# SX-150_Mk_II.net
KiCad netlist of a schematic drawn in EAGLE
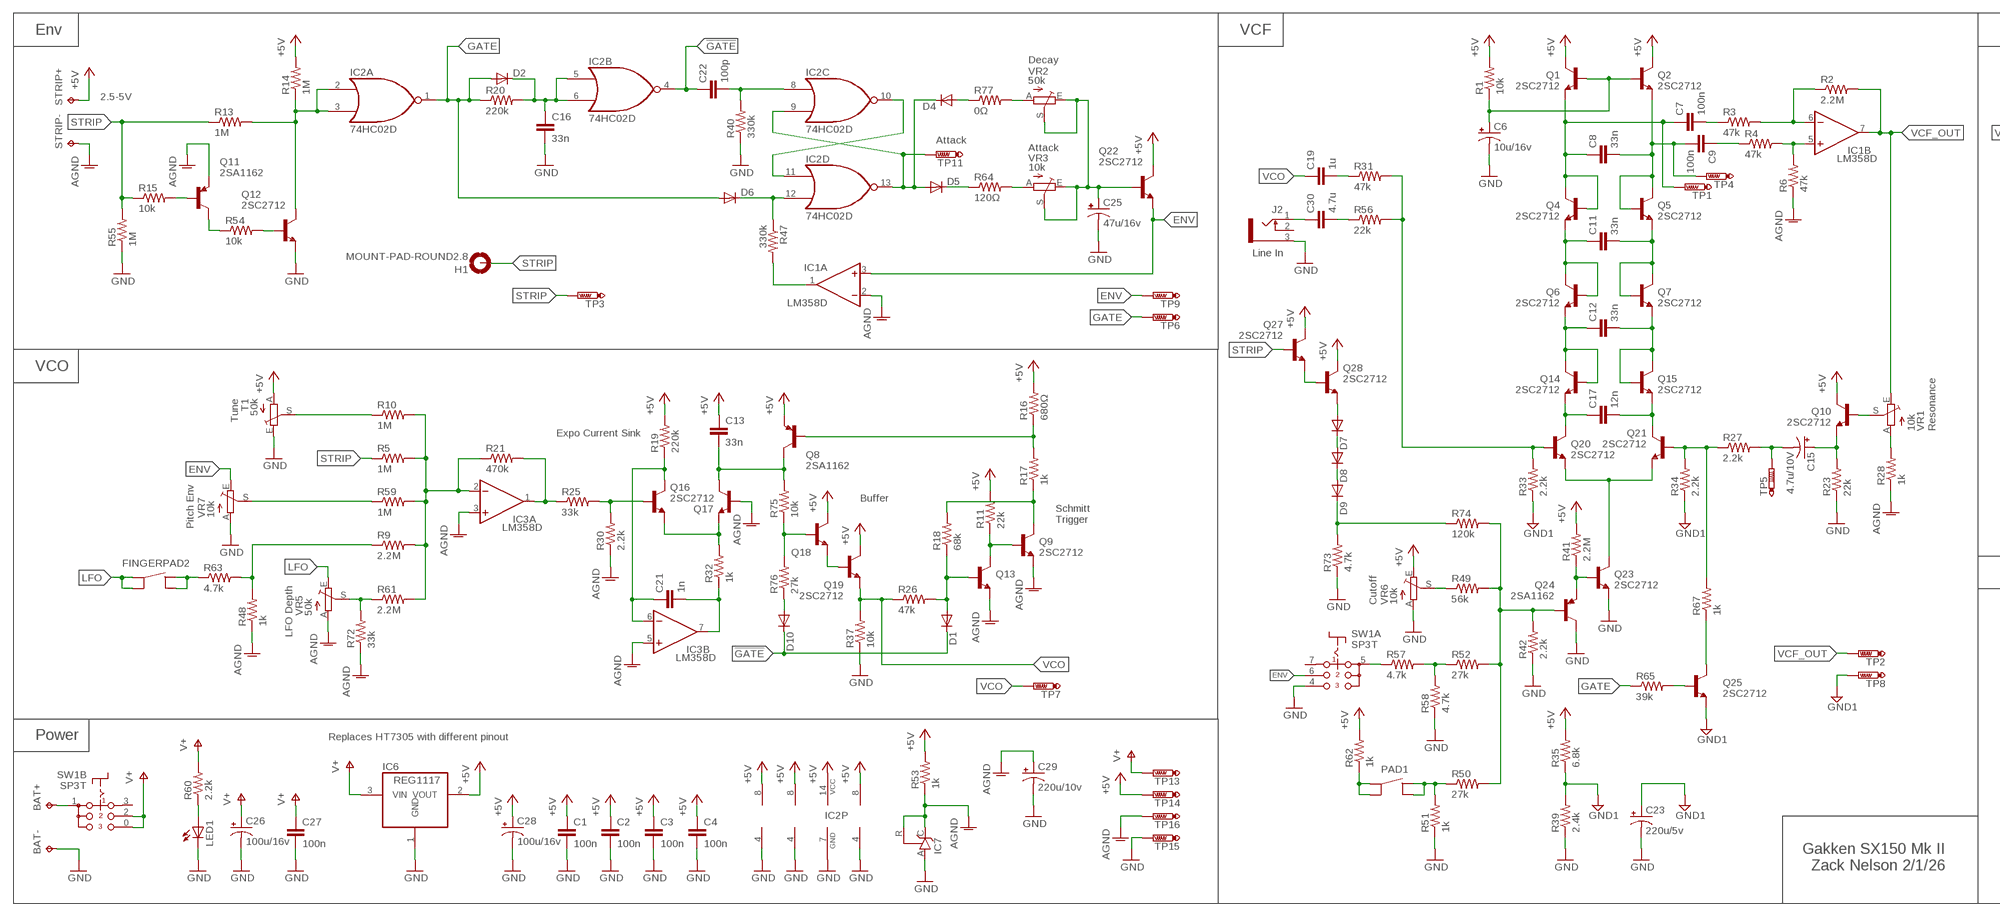
[diagram p0: schematic, sheet 1, part 1 of 2]
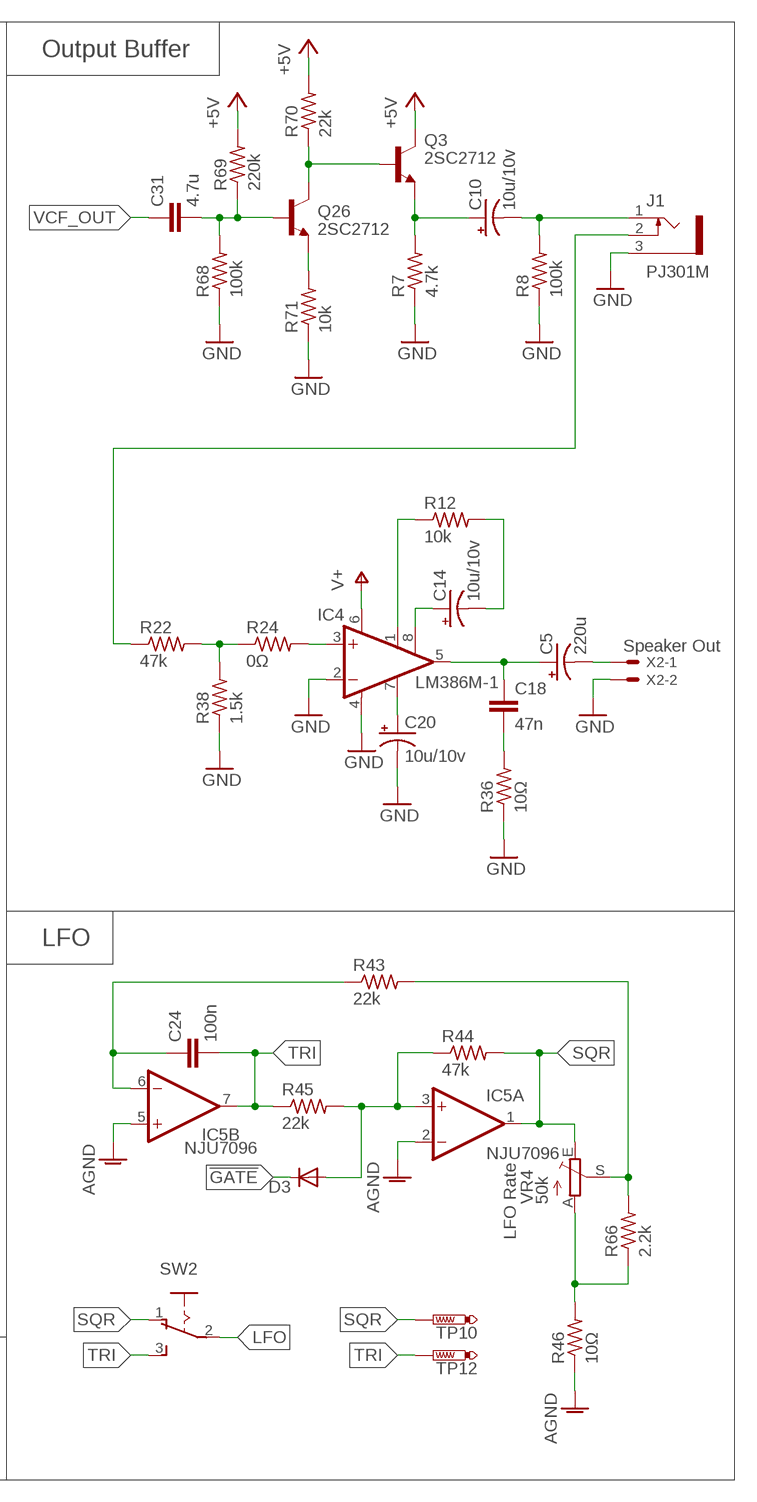
[diagram p1: schematic, sheet 1, part 2 of 2]

(export (version "E")
  (design (tool "Eeschema 10.0.6"))
  (components
    (comp (ref "BAT+")
      (value "TPPAD1-13")
      (footprint "eagle-import:P1-13")
      (libsource (lib "eagle-import") (part "TPPAD1-13"))
    )
    (comp (ref "BAT-")
      (value "TPPAD1-13")
      (footprint "eagle-import:P1-13")
      (libsource (lib "eagle-import") (part "TPPAD1-13"))
    )
    (comp (ref "C1")
      (value "100n")
      (footprint "eagle-import:C0603")
      (libsource (lib "eagle-import") (part "C-EUC0603"))
    )
    (comp (ref "C2")
      (value "100n")
      (footprint "eagle-import:C0603")
      (libsource (lib "eagle-import") (part "C-EUC0603"))
    )
    (comp (ref "C3")
      (value "100n")
      (footprint "eagle-import:C0603")
      (libsource (lib "eagle-import") (part "C-EUC0603"))
    )
    (comp (ref "C4")
      (value "100n")
      (footprint "eagle-import:C0603")
      (libsource (lib "eagle-import") (part "C-EUC0603"))
    )
    (comp (ref "C5")
      (value "220u")
      (footprint "eagle-import:E2,5-6")
      (libsource (lib "eagle-import") (part "CPOL-USE2.5-6"))
    )
    (comp (ref "C6")
      (value "10u/16v")
      (footprint "eagle-import:E2,5-6")
      (libsource (lib "eagle-import") (part "CPOL-USE2.5-6"))
    )
    (comp (ref "C7")
      (value "100n")
      (footprint "eagle-import:C0603")
      (libsource (lib "eagle-import") (part "C-EUC0603"))
    )
    (comp (ref "C8")
      (value "33n")
      (footprint "eagle-import:C0603")
      (libsource (lib "eagle-import") (part "C-EUC0603"))
    )
    (comp (ref "C9")
      (value "100n")
      (footprint "eagle-import:C0603")
      (libsource (lib "eagle-import") (part "C-EUC0603"))
    )
    (comp (ref "C10")
      (value "10u/10v")
      (footprint "eagle-import:E2,5-6")
      (libsource (lib "eagle-import") (part "CPOL-USE2.5-6"))
    )
    (comp (ref "C11")
      (value "33n")
      (footprint "eagle-import:C0603")
      (libsource (lib "eagle-import") (part "C-EUC0603"))
    )
    (comp (ref "C12")
      (value "33n")
      (footprint "eagle-import:C0603")
      (libsource (lib "eagle-import") (part "C-EUC0603"))
    )
    (comp (ref "C13")
      (value "33n")
      (footprint "eagle-import:C0603")
      (libsource (lib "eagle-import") (part "C-EUC0603"))
    )
    (comp (ref "C14")
      (value "10u/10v")
      (footprint "eagle-import:E2,5-6")
      (libsource (lib "eagle-import") (part "CPOL-USE2.5-6"))
    )
    (comp (ref "C15")
      (value "4.7u/10V")
      (footprint "eagle-import:E2,5-6")
      (libsource (lib "eagle-import") (part "CPOL-USE2.5-6"))
    )
    (comp (ref "C16")
      (value "33n")
      (footprint "eagle-import:C0603")
      (libsource (lib "eagle-import") (part "C-EUC0603"))
    )
    (comp (ref "C17")
      (value "12n")
      (footprint "eagle-import:C0603")
      (libsource (lib "eagle-import") (part "C-EUC0603"))
    )
    (comp (ref "C18")
      (value "47n")
      (footprint "eagle-import:C0603")
      (libsource (lib "eagle-import") (part "C-EUC0603"))
    )
    (comp (ref "C19")
      (value "1u")
      (footprint "eagle-import:C0603")
      (libsource (lib "eagle-import") (part "C-EUC0603"))
    )
    (comp (ref "C20")
      (value "10u/10v")
      (footprint "eagle-import:E2,5-6")
      (libsource (lib "eagle-import") (part "CPOL-USE2.5-6"))
    )
    (comp (ref "C21")
      (value "1n")
      (footprint "eagle-import:C0603")
      (libsource (lib "eagle-import") (part "C-EUC0603"))
    )
    (comp (ref "C22")
      (value "100p")
      (footprint "eagle-import:C0603")
      (libsource (lib "eagle-import") (part "C-EUC0603"))
    )
    (comp (ref "C23")
      (value "220u/5v")
      (footprint "eagle-import:E2,5-6")
      (libsource (lib "eagle-import") (part "CPOL-USE2.5-6"))
    )
    (comp (ref "C24")
      (value "100n")
      (footprint "eagle-import:C0603")
      (libsource (lib "eagle-import") (part "C-EUC0603"))
    )
    (comp (ref "C25")
      (value "47u/16v")
      (footprint "eagle-import:E2,5-6")
      (libsource (lib "eagle-import") (part "CPOL-USE2.5-6"))
    )
    (comp (ref "C26")
      (value "100u/16v")
      (footprint "eagle-import:E2,5-6")
      (libsource (lib "eagle-import") (part "CPOL-USE2.5-6"))
    )
    (comp (ref "C27")
      (value "100n")
      (footprint "eagle-import:C0603")
      (libsource (lib "eagle-import") (part "C-EUC0603"))
    )
    (comp (ref "C28")
      (value "100u/16v")
      (footprint "eagle-import:E2,5-6")
      (libsource (lib "eagle-import") (part "CPOL-USE2.5-6"))
    )
    (comp (ref "C29")
      (value "220u/10v")
      (footprint "eagle-import:E2,5-6")
      (libsource (lib "eagle-import") (part "CPOL-USE2.5-6"))
    )
    (comp (ref "C30")
      (value "4.7u")
      (footprint "eagle-import:C0603")
      (libsource (lib "eagle-import") (part "C-EUC0603"))
    )
    (comp (ref "C31")
      (value "4.7u")
      (footprint "eagle-import:C0603")
      (libsource (lib "eagle-import") (part "C-EUC0603"))
    )
    (comp (ref "D1")
      (value "DIODE-DO41-7.6")
      (footprint "eagle-import:DO41-7.6")
      (libsource (lib "eagle-import") (part "DIODE-DO41-7.6"))
    )
    (comp (ref "D2")
      (value "DIODE-MINIMELF")
      (footprint "eagle-import:MINIMELF")
      (libsource (lib "eagle-import") (part "DIODE-MINIMELF"))
    )
    (comp (ref "D3")
      (value "DIODE-MINIMELF")
      (footprint "eagle-import:MINIMELF")
      (libsource (lib "eagle-import") (part "DIODE-MINIMELF"))
    )
    (comp (ref "D4")
      (value "DIODE-MINIMELF")
      (footprint "eagle-import:MINIMELF")
      (libsource (lib "eagle-import") (part "DIODE-MINIMELF"))
    )
    (comp (ref "D5")
      (value "DIODE-MINIMELF")
      (footprint "eagle-import:MINIMELF")
      (libsource (lib "eagle-import") (part "DIODE-MINIMELF"))
    )
    (comp (ref "D6")
      (value "DIODE-MINIMELF")
      (footprint "eagle-import:MINIMELF")
      (libsource (lib "eagle-import") (part "DIODE-MINIMELF"))
    )
    (comp (ref "D7")
      (value "DIODE-MINIMELF")
      (footprint "eagle-import:MINIMELF")
      (libsource (lib "eagle-import") (part "DIODE-MINIMELF"))
    )
    (comp (ref "D8")
      (value "DIODE-MINIMELF")
      (footprint "eagle-import:MINIMELF")
      (libsource (lib "eagle-import") (part "DIODE-MINIMELF"))
    )
    (comp (ref "D9")
      (value "DIODE-MINIMELF")
      (footprint "eagle-import:MINIMELF")
      (libsource (lib "eagle-import") (part "DIODE-MINIMELF"))
    )
    (comp (ref "D10")
      (value "DIODE-DO41-7.6")
      (footprint "eagle-import:DO41-7.6")
      (libsource (lib "eagle-import") (part "DIODE-DO41-7.6"))
    )
    (comp (ref "FINGERPAD2")
      (value "GAKKEN-PAD")
      (footprint "eagle-import:GAKKEN-PAD")
      (libsource (lib "eagle-import") (part "GAKKEN-PAD"))
    )
    (comp (ref "H1")
      (value "MOUNT-PAD-ROUND2.8")
      (footprint "eagle-import:2,8-PAD")
      (libsource (lib "eagle-import") (part "MOUNT-PAD-ROUND2.8"))
    )
    (comp (ref "IC1")
      (value "LM358D")
      (footprint "eagle-import:SO08")
      (libsource (lib "eagle-import") (part "LM358D"))
    )
    (comp (ref "IC2")
      (value "74HC02D")
      (footprint "eagle-import:SO14")
      (libsource (lib "eagle-import") (part "7402D"))
    )
    (comp (ref "IC3")
      (value "LM358D")
      (footprint "eagle-import:SO08")
      (libsource (lib "eagle-import") (part "LM358D"))
    )
    (comp (ref "IC4")
      (value "LM386M-1")
      (footprint "eagle-import:SO08")
      (libsource (lib "eagle-import") (part "LM386?-M1"))
    )
    (comp (ref "IC5")
      (value "NJU7096")
      (footprint "eagle-import:SO08")
      (libsource (lib "eagle-import") (part "LM358D"))
    )
    (comp (ref "IC6")
      (value "REG1117")
      (footprint "eagle-import:SOT223")
      (libsource (lib "eagle-import") (part "REG1117"))
    )
    (comp (ref "IC7")
      (value "TL431CLP")
      (footprint "eagle-import:TO92-CLP")
      (libsource (lib "eagle-import") (part "TL431CLP"))
    )
    (comp (ref "J1")
      (value "PJ301M")
      (footprint "eagle-import:JACK-3.5-NOHOLE")
      (libsource (lib "eagle-import") (part "WQP_PJ301M-12_JACK"))
    )
    (comp (ref "J2")
      (value "Line In")
      (footprint "eagle-import:JACK-3.5-NOHOLE")
      (libsource (lib "eagle-import") (part "WQP_PJ301M-12_JACK"))
    )
    (comp (ref "LED1")
      (value "LED3MM")
      (footprint "eagle-import:LED3MM")
      (libsource (lib "eagle-import") (part "LED3MM"))
    )
    (comp (ref "PAD1")
      (value "GAKKEN-PAD")
      (footprint "eagle-import:GAKKEN-PAD")
      (libsource (lib "eagle-import") (part "GAKKEN-PAD"))
    )
    (comp (ref "Q1")
      (value "2SC2712")
      (footprint "eagle-import:SOT23-BEC")
      (libsource (lib "eagle-import") (part "-NPN-SOT23-BECBC808"))
    )
    (comp (ref "Q2")
      (value "2SC2712")
      (footprint "eagle-import:SOT23-BEC")
      (libsource (lib "eagle-import") (part "-NPN-SOT23-BECBC808"))
    )
    (comp (ref "Q3")
      (value "2SC2712")
      (footprint "eagle-import:SOT23-BEC")
      (libsource (lib "eagle-import") (part "-NPN-SOT23-BECBC808"))
    )
    (comp (ref "Q4")
      (value "2SC2712")
      (footprint "eagle-import:SOT23-BEC")
      (libsource (lib "eagle-import") (part "-NPN-SOT23-BECBC808"))
    )
    (comp (ref "Q5")
      (value "2SC2712")
      (footprint "eagle-import:SOT23-BEC")
      (libsource (lib "eagle-import") (part "-NPN-SOT23-BECBC808"))
    )
    (comp (ref "Q6")
      (value "2SC2712")
      (footprint "eagle-import:SOT23-BEC")
      (libsource (lib "eagle-import") (part "-NPN-SOT23-BECBC808"))
    )
    (comp (ref "Q7")
      (value "2SC2712")
      (footprint "eagle-import:SOT23-BEC")
      (libsource (lib "eagle-import") (part "-NPN-SOT23-BECBC808"))
    )
    (comp (ref "Q8")
      (value "2SA1162")
      (footprint "eagle-import:SOT23-BEC")
      (libsource (lib "eagle-import") (part "-PNP-SOT23-BECBC807-16"))
    )
    (comp (ref "Q9")
      (value "2SC2712")
      (footprint "eagle-import:SOT23-BEC")
      (libsource (lib "eagle-import") (part "-NPN-SOT23-BECBC808"))
    )
    (comp (ref "Q10")
      (value "2SC2712")
      (footprint "eagle-import:SOT23-BEC")
      (libsource (lib "eagle-import") (part "-NPN-SOT23-BECBC808"))
    )
    (comp (ref "Q11")
      (value "2SA1162")
      (footprint "eagle-import:SOT23-BEC")
      (libsource (lib "eagle-import") (part "-PNP-SOT23-BECBC807-16"))
    )
    (comp (ref "Q12")
      (value "2SC2712")
      (footprint "eagle-import:SOT23-BEC")
      (libsource (lib "eagle-import") (part "-NPN-SOT23-BECBC808"))
    )
    (comp (ref "Q13")
      (value "2SC2712")
      (footprint "eagle-import:SOT23-BEC")
      (libsource (lib "eagle-import") (part "-NPN-SOT23-BECBC808"))
    )
    (comp (ref "Q14")
      (value "2SC2712")
      (footprint "eagle-import:SOT23-BEC")
      (libsource (lib "eagle-import") (part "-NPN-SOT23-BECBC808"))
    )
    (comp (ref "Q15")
      (value "2SC2712")
      (footprint "eagle-import:SOT23-BEC")
      (libsource (lib "eagle-import") (part "-NPN-SOT23-BECBC808"))
    )
    (comp (ref "Q16")
      (value "2SC2712")
      (footprint "eagle-import:SOT23-BEC")
      (libsource (lib "eagle-import") (part "-NPN-SOT23-BECBC808"))
    )
    (comp (ref "Q17")
      (value "2SC2712")
      (footprint "eagle-import:SOT23-BEC")
      (libsource (lib "eagle-import") (part "-NPN-SOT23-BECBC808"))
    )
    (comp (ref "Q18")
      (value "2SC2712")
      (footprint "eagle-import:SOT23-BEC")
      (libsource (lib "eagle-import") (part "-NPN-SOT23-BECBC808"))
    )
    (comp (ref "Q19")
      (value "2SC2712")
      (footprint "eagle-import:SOT23-BEC")
      (libsource (lib "eagle-import") (part "-NPN-SOT23-BECBC808"))
    )
    (comp (ref "Q20")
      (value "2SC2712")
      (footprint "eagle-import:SOT23-BEC")
      (libsource (lib "eagle-import") (part "-NPN-SOT23-BECBC808"))
    )
    (comp (ref "Q21")
      (value "2SC2712")
      (footprint "eagle-import:SOT23-BEC")
      (libsource (lib "eagle-import") (part "-NPN-SOT23-BECBC808"))
    )
    (comp (ref "Q22")
      (value "2SC2712")
      (footprint "eagle-import:SOT23-BEC")
      (libsource (lib "eagle-import") (part "-NPN-SOT23-BECBC808"))
    )
    (comp (ref "Q23")
      (value "2SC2712")
      (footprint "eagle-import:SOT23-BEC")
      (libsource (lib "eagle-import") (part "-NPN-SOT23-BECBC808"))
    )
    (comp (ref "Q24")
      (value "2SA1162")
      (footprint "eagle-import:SOT23-BEC")
      (libsource (lib "eagle-import") (part "-PNP-SOT23-BECBC807-16"))
    )
    (comp (ref "Q25")
      (value "2SC2712")
      (footprint "eagle-import:SOT23-BEC")
      (libsource (lib "eagle-import") (part "-NPN-SOT23-BECBC808"))
    )
    (comp (ref "Q26")
      (value "2SC2712")
      (footprint "eagle-import:SOT23-BEC")
      (libsource (lib "eagle-import") (part "-NPN-SOT23-BECBC808"))
    )
    (comp (ref "Q27")
      (value "2SC2712")
      (footprint "eagle-import:SOT23-BEC")
      (libsource (lib "eagle-import") (part "-NPN-SOT23-BECBC808"))
    )
    (comp (ref "Q28")
      (value "2SC2712")
      (footprint "eagle-import:SOT23-BEC")
      (libsource (lib "eagle-import") (part "-NPN-SOT23-BECBC808"))
    )
    (comp (ref "R1")
      (value "10k")
      (footprint "eagle-import:R0603")
      (libsource (lib "eagle-import") (part "R-US_R0603"))
    )
    (comp (ref "R2")
      (value "2.2M")
      (footprint "eagle-import:R0603")
      (libsource (lib "eagle-import") (part "R-US_R0603"))
    )
    (comp (ref "R3")
      (value "47k")
      (footprint "eagle-import:R0603")
      (libsource (lib "eagle-import") (part "R-US_R0603"))
    )
    (comp (ref "R4")
      (value "47k")
      (footprint "eagle-import:R0603")
      (libsource (lib "eagle-import") (part "R-US_R0603"))
    )
    (comp (ref "R5")
      (value "1M")
      (footprint "eagle-import:R0603")
      (libsource (lib "eagle-import") (part "R-US_R0603"))
    )
    (comp (ref "R6")
      (value "47k")
      (footprint "eagle-import:R0603")
      (libsource (lib "eagle-import") (part "R-US_R0603"))
    )
    (comp (ref "R7")
      (value "4.7k")
      (footprint "eagle-import:R0603")
      (libsource (lib "eagle-import") (part "R-US_R0603"))
    )
    (comp (ref "R8")
      (value "100k")
      (footprint "eagle-import:R0603")
      (libsource (lib "eagle-import") (part "R-US_R0603"))
    )
    (comp (ref "R9")
      (value "2.2M")
      (footprint "eagle-import:R0603")
      (libsource (lib "eagle-import") (part "R-US_R0603"))
    )
    (comp (ref "R10")
      (value "1M")
      (footprint "eagle-import:R0603")
      (libsource (lib "eagle-import") (part "R-US_R0603"))
    )
    (comp (ref "R11")
      (value "22k")
      (footprint "eagle-import:R0603")
      (libsource (lib "eagle-import") (part "R-US_R0603"))
    )
    (comp (ref "R12")
      (value "10k")
      (footprint "eagle-import:R0603")
      (libsource (lib "eagle-import") (part "R-US_R0603"))
    )
    (comp (ref "R13")
      (value "1M")
      (footprint "eagle-import:R0603")
      (libsource (lib "eagle-import") (part "R-US_R0603"))
    )
    (comp (ref "R14")
      (value "1M")
      (footprint "eagle-import:R0603")
      (libsource (lib "eagle-import") (part "R-US_R0603"))
    )
    (comp (ref "R15")
      (value "10k")
      (footprint "eagle-import:R0603")
      (libsource (lib "eagle-import") (part "R-US_R0603"))
    )
    (comp (ref "R16")
      (value "680Ω")
      (footprint "eagle-import:R0603")
      (libsource (lib "eagle-import") (part "R-US_R0603"))
    )
    (comp (ref "R17")
      (value "1k")
      (footprint "eagle-import:R0603")
      (libsource (lib "eagle-import") (part "R-US_R0603"))
    )
    (comp (ref "R18")
      (value "68k")
      (footprint "eagle-import:R0603")
      (libsource (lib "eagle-import") (part "R-US_R0603"))
    )
    (comp (ref "R19")
      (value "220k")
      (footprint "eagle-import:R0603")
      (libsource (lib "eagle-import") (part "R-US_R0603"))
    )
    (comp (ref "R20")
      (value "220k")
      (footprint "eagle-import:R0603")
      (libsource (lib "eagle-import") (part "R-US_R0603"))
    )
    (comp (ref "R21")
      (value "470k")
      (footprint "eagle-import:R0603")
      (libsource (lib "eagle-import") (part "R-US_R0603"))
    )
    (comp (ref "R22")
      (value "47k")
      (footprint "eagle-import:R0603")
      (libsource (lib "eagle-import") (part "R-US_R0603"))
    )
    (comp (ref "R23")
      (value "22k")
      (footprint "eagle-import:R0603")
      (libsource (lib "eagle-import") (part "R-US_R0603"))
    )
    (comp (ref "R24")
      (value "0Ω")
      (footprint "eagle-import:R0603")
      (libsource (lib "eagle-import") (part "R-US_R0603"))
    )
    (comp (ref "R25")
      (value "33k")
      (footprint "eagle-import:R0603")
      (libsource (lib "eagle-import") (part "R-US_R0603"))
    )
    (comp (ref "R26")
      (value "47k")
      (footprint "eagle-import:R0603")
      (libsource (lib "eagle-import") (part "R-US_R0603"))
    )
    (comp (ref "R27")
      (value "2.2k")
      (footprint "eagle-import:R0603")
      (libsource (lib "eagle-import") (part "R-US_R0603"))
    )
    (comp (ref "R28")
      (value "1k")
      (footprint "eagle-import:R0603")
      (libsource (lib "eagle-import") (part "R-US_R0603"))
    )
    (comp (ref "R30")
      (value "2.2k")
      (footprint "eagle-import:R0603")
      (libsource (lib "eagle-import") (part "R-US_R0603"))
    )
    (comp (ref "R31")
      (value "47k")
      (footprint "eagle-import:R0603")
      (libsource (lib "eagle-import") (part "R-US_R0603"))
    )
    (comp (ref "R32")
      (value "1k")
      (footprint "eagle-import:R0603")
      (libsource (lib "eagle-import") (part "R-US_R0603"))
    )
    (comp (ref "R33")
      (value "2.2k")
      (footprint "eagle-import:R0603")
      (libsource (lib "eagle-import") (part "R-US_R0603"))
    )
    (comp (ref "R34")
      (value "2.2k")
      (footprint "eagle-import:R0603")
      (libsource (lib "eagle-import") (part "R-US_R0603"))
    )
    (comp (ref "R35")
      (value "6.8k")
      (footprint "eagle-import:R0603")
      (libsource (lib "eagle-import") (part "R-US_R0603"))
    )
    (comp (ref "R36")
      (value "10Ω")
      (footprint "eagle-import:R0603")
      (libsource (lib "eagle-import") (part "R-US_R0603"))
    )
    (comp (ref "R37")
      (value "10k")
      (footprint "eagle-import:R0603")
      (libsource (lib "eagle-import") (part "R-US_R0603"))
    )
    (comp (ref "R38")
      (value "1.5k")
      (footprint "eagle-import:R0603")
      (libsource (lib "eagle-import") (part "R-US_R0603"))
    )
    (comp (ref "R39")
      (value "2.4k")
      (footprint "eagle-import:R0603")
      (libsource (lib "eagle-import") (part "R-US_R0603"))
    )
    (comp (ref "R40")
      (value "330k")
      (footprint "eagle-import:R0603")
      (libsource (lib "eagle-import") (part "R-US_R0603"))
    )
    (comp (ref "R41")
      (value "2.2M")
      (footprint "eagle-import:R0603")
      (libsource (lib "eagle-import") (part "R-US_R0603"))
    )
    (comp (ref "R42")
      (value "2.2k")
      (footprint "eagle-import:R0603")
      (libsource (lib "eagle-import") (part "R-US_R0603"))
    )
    (comp (ref "R43")
      (value "22k")
      (footprint "eagle-import:R0603")
      (libsource (lib "eagle-import") (part "R-US_R0603"))
    )
    (comp (ref "R44")
      (value "47k")
      (footprint "eagle-import:R0603")
      (libsource (lib "eagle-import") (part "R-US_R0603"))
    )
    (comp (ref "R45")
      (value "22k")
      (footprint "eagle-import:R0603")
      (libsource (lib "eagle-import") (part "R-US_R0603"))
    )
    (comp (ref "R46")
      (value "10Ω")
      (footprint "eagle-import:R0603")
      (libsource (lib "eagle-import") (part "R-US_R0603"))
    )
    (comp (ref "R47")
      (value "330k")
      (footprint "eagle-import:R0603")
      (libsource (lib "eagle-import") (part "R-US_R0603"))
    )
    (comp (ref "R48")
      (value "1k")
      (footprint "eagle-import:R0603")
      (libsource (lib "eagle-import") (part "R-US_R0603"))
    )
    (comp (ref "R49")
      (value "56k")
      (footprint "eagle-import:R0603")
      (libsource (lib "eagle-import") (part "R-US_R0603"))
    )
    (comp (ref "R50")
      (value "27k")
      (footprint "eagle-import:R0603")
      (libsource (lib "eagle-import") (part "R-US_R0603"))
    )
    (comp (ref "R51")
      (value "1k")
      (footprint "eagle-import:R0603")
      (libsource (lib "eagle-import") (part "R-US_R0603"))
    )
    (comp (ref "R52")
      (value "27k")
      (footprint "eagle-import:R0603")
      (libsource (lib "eagle-import") (part "R-US_R0603"))
    )
    (comp (ref "R53")
      (value "1k")
      (footprint "eagle-import:R0603")
      (libsource (lib "eagle-import") (part "R-US_R0603"))
    )
    (comp (ref "R54")
      (value "10k")
      (footprint "eagle-import:R0603")
      (libsource (lib "eagle-import") (part "R-US_R0603"))
    )
    (comp (ref "R55")
      (value "1M")
      (footprint "eagle-import:R0603")
      (libsource (lib "eagle-import") (part "R-US_R0603"))
    )
    (comp (ref "R56")
      (value "22k")
      (footprint "eagle-import:R0603")
      (libsource (lib "eagle-import") (part "R-US_R0603"))
    )
    (comp (ref "R57")
      (value "4.7k")
      (footprint "eagle-import:R0603")
      (libsource (lib "eagle-import") (part "R-US_R0603"))
    )
    (comp (ref "R58")
      (value "4.7k")
      (footprint "eagle-import:R0603")
      (libsource (lib "eagle-import") (part "R-US_R0603"))
    )
    (comp (ref "R59")
      (value "1M")
      (footprint "eagle-import:R0603")
      (libsource (lib "eagle-import") (part "R-US_R0603"))
    )
    (comp (ref "R60")
      (value "2.2k")
      (footprint "eagle-import:R0603")
      (libsource (lib "eagle-import") (part "R-US_R0603"))
    )
    (comp (ref "R61")
      (value "2.2M")
      (footprint "eagle-import:R0603")
      (libsource (lib "eagle-import") (part "R-US_R0603"))
    )
    (comp (ref "R62")
      (value "1k")
      (footprint "eagle-import:R0603")
      (libsource (lib "eagle-import") (part "R-US_R0603"))
    )
    (comp (ref "R63")
      (value "4.7k")
      (footprint "eagle-import:R0603")
      (libsource (lib "eagle-import") (part "R-US_R0603"))
    )
    (comp (ref "R64")
      (value "120Ω")
      (footprint "eagle-import:R0603")
      (libsource (lib "eagle-import") (part "R-US_R0603"))
    )
    (comp (ref "R65")
      (value "39k")
      (footprint "eagle-import:R0603")
      (libsource (lib "eagle-import") (part "R-US_R0603"))
    )
    (comp (ref "R66")
      (value "2.2k")
      (footprint "eagle-import:R0603")
      (libsource (lib "eagle-import") (part "R-US_R0603"))
    )
    (comp (ref "R67")
      (value "1k")
      (footprint "eagle-import:R0603")
      (libsource (lib "eagle-import") (part "R-US_R0603"))
    )
    (comp (ref "R68")
      (value "100k")
      (footprint "eagle-import:R0603")
      (libsource (lib "eagle-import") (part "R-US_R0603"))
    )
    (comp (ref "R69")
      (value "220k")
      (footprint "eagle-import:R0603")
      (libsource (lib "eagle-import") (part "R-US_R0603"))
    )
    (comp (ref "R70")
      (value "22k")
      (footprint "eagle-import:R0603")
      (libsource (lib "eagle-import") (part "R-US_R0603"))
    )
    (comp (ref "R71")
      (value "10k")
      (footprint "eagle-import:R0603")
      (libsource (lib "eagle-import") (part "R-US_R0603"))
    )
    (comp (ref "R72")
      (value "33k")
      (footprint "eagle-import:R0603")
      (libsource (lib "eagle-import") (part "R-US_R0603"))
    )
    (comp (ref "R73")
      (value "4.7k")
      (footprint "eagle-import:R0603")
      (libsource (lib "eagle-import") (part "R-US_R0603"))
    )
    (comp (ref "R74")
      (value "120k")
      (footprint "eagle-import:R0603")
      (libsource (lib "eagle-import") (part "R-US_R0603"))
    )
    (comp (ref "R75")
      (value "10k")
      (footprint "eagle-import:R0603")
      (libsource (lib "eagle-import") (part "R-US_R0603"))
    )
    (comp (ref "R76")
      (value "27k")
      (footprint "eagle-import:R0603")
      (libsource (lib "eagle-import") (part "R-US_R0603"))
    )
    (comp (ref "R77")
      (value "0Ω")
      (footprint "eagle-import:R0603")
      (libsource (lib "eagle-import") (part "R-US_R0603"))
    )
    (comp (ref "STRIP+")
      (value "TPB1,27")
      (footprint "eagle-import:B1,27")
      (libsource (lib "eagle-import") (part "TPB1,27"))
    )
    (comp (ref "STRIP-")
      (value "TPB1,27")
      (footprint "eagle-import:B1,27")
      (libsource (lib "eagle-import") (part "TPB1,27"))
    )
    (comp (ref "SW1")
      (value "SP3T")
      (footprint "eagle-import:SP3T")
      (libsource (lib "eagle-import") (part "SP3T"))
    )
    (comp (ref "SW2")
      (value "M251")
      (footprint "eagle-import:M251")
      (libsource (lib "eagle-import") (part "M251"))
    )
    (comp (ref "T1")
      (value "50k")
      (footprint "eagle-import:CA9V")
      (libsource (lib "eagle-import") (part "TRIM_EU-CA9V"))
    )
    (comp (ref "TP1")
      (value "PTR1B1,27")
      (footprint "eagle-import:B1,27")
      (libsource (lib "eagle-import") (part "PTR1B1,27"))
    )
    (comp (ref "TP2")
      (value "PTR1B1,27")
      (footprint "eagle-import:B1,27")
      (libsource (lib "eagle-import") (part "PTR1B1,27"))
    )
    (comp (ref "TP3")
      (value "PTR1B1,27")
      (footprint "eagle-import:B1,27")
      (libsource (lib "eagle-import") (part "PTR1B1,27"))
    )
    (comp (ref "TP4")
      (value "PTR1B1,27")
      (footprint "eagle-import:B1,27")
      (libsource (lib "eagle-import") (part "PTR1B1,27"))
    )
    (comp (ref "TP5")
      (value "PTR1B1,27")
      (footprint "eagle-import:B1,27")
      (libsource (lib "eagle-import") (part "PTR1B1,27"))
    )
    (comp (ref "TP6")
      (value "PTR1B1,27")
      (footprint "eagle-import:B1,27")
      (libsource (lib "eagle-import") (part "PTR1B1,27"))
    )
    (comp (ref "TP7")
      (value "PTR1B1,27")
      (footprint "eagle-import:B1,27")
      (libsource (lib "eagle-import") (part "PTR1B1,27"))
    )
    (comp (ref "TP8")
      (value "PTR1B1,27")
      (footprint "eagle-import:B1,27")
      (libsource (lib "eagle-import") (part "PTR1B1,27"))
    )
    (comp (ref "TP9")
      (value "PTR1B1,27")
      (footprint "eagle-import:B1,27")
      (libsource (lib "eagle-import") (part "PTR1B1,27"))
    )
    (comp (ref "TP10")
      (value "PTR1B1,27")
      (footprint "eagle-import:B1,27")
      (libsource (lib "eagle-import") (part "PTR1B1,27"))
    )
    (comp (ref "TP11")
      (value "PTR1B1,27")
      (footprint "eagle-import:B1,27")
      (libsource (lib "eagle-import") (part "PTR1B1,27"))
    )
    (comp (ref "TP12")
      (value "PTR1B1,27")
      (footprint "eagle-import:B1,27")
      (libsource (lib "eagle-import") (part "PTR1B1,27"))
    )
    (comp (ref "TP13")
      (value "PTR1B1,27")
      (footprint "eagle-import:B1,27")
      (libsource (lib "eagle-import") (part "PTR1B1,27"))
    )
    (comp (ref "TP14")
      (value "PTR1B1,27")
      (footprint "eagle-import:B1,27")
      (libsource (lib "eagle-import") (part "PTR1B1,27"))
    )
    (comp (ref "TP15")
      (value "PTR1B1,27")
      (footprint "eagle-import:B1,27")
      (libsource (lib "eagle-import") (part "PTR1B1,27"))
    )
    (comp (ref "TP16")
      (value "PTR1B1,27")
      (footprint "eagle-import:B1,27")
      (libsource (lib "eagle-import") (part "PTR1B1,27"))
    )
    (comp (ref "VR1")
      (value "10k")
      (footprint "eagle-import:CA9V")
      (libsource (lib "eagle-import") (part "TRIM_EU-CA9V"))
    )
    (comp (ref "VR2")
      (value "50k")
      (footprint "eagle-import:CA9V")
      (libsource (lib "eagle-import") (part "TRIM_EU-CA9V"))
    )
    (comp (ref "VR3")
      (value "10k")
      (footprint "eagle-import:CA9V")
      (libsource (lib "eagle-import") (part "TRIM_EU-CA9V"))
    )
    (comp (ref "VR4")
      (value "50k")
      (footprint "eagle-import:CA9V")
      (libsource (lib "eagle-import") (part "TRIM_EU-CA9V"))
    )
    (comp (ref "VR5")
      (value "50k")
      (footprint "eagle-import:CA9V")
      (libsource (lib "eagle-import") (part "TRIM_EU-CA9V"))
    )
    (comp (ref "VR6")
      (value "10k")
      (footprint "eagle-import:CA9V")
      (libsource (lib "eagle-import") (part "TRIM_EU-CA9V"))
    )
    (comp (ref "VR7")
      (value "10k")
      (footprint "eagle-import:CA9V")
      (libsource (lib "eagle-import") (part "TRIM_EU-CA9V"))
    )
    (comp (ref "X2")
      (value "Speaker Out")
      (footprint "eagle-import:22-23-2021")
      (fields (field (name "MF") "MOLEX") (field (name "MPN") "22-23-2021"))
      (libsource (lib "eagle-import") (part "22-23-2021"))
    )
  )
  (nets
    (net (code "1") (name "+5V") (class "Default")
      (node (ref "C1") (pin "1") (pinfunction "1_1") (pintype "passive"))
      (node (ref "C13") (pin "1") (pinfunction "1_1") (pintype "passive"))
      (node (ref "C2") (pin "1") (pinfunction "1_1") (pintype "passive"))
      (node (ref "C28") (pin "+") (pinfunction "+_+") (pintype "passive"))
      (node (ref "C3") (pin "1") (pinfunction "1_1") (pintype "passive"))
      (node (ref "C4") (pin "1") (pinfunction "1_1") (pintype "passive"))
      (node (ref "IC1") (pin "8") (pinfunction "V+_8") (pintype "power_in"))
      (node (ref "IC2") (pin "14") (pinfunction "VCC_14") (pintype "power_in"))
      (node (ref "IC3") (pin "8") (pinfunction "V+_8") (pintype "power_in"))
      (node (ref "IC5") (pin "8") (pinfunction "V+_8") (pintype "power_in"))
      (node (ref "IC6") (pin "2") (pinfunction "VOUT_2") (pintype "output"))
      (node (ref "Q1") (pin "C") (pinfunction "C_C") (pintype "passive"))
      (node (ref "Q10") (pin "C") (pinfunction "C_C") (pintype "passive"))
      (node (ref "Q18") (pin "C") (pinfunction "C_C") (pintype "passive"))
      (node (ref "Q19") (pin "C") (pinfunction "C_C") (pintype "passive"))
      (node (ref "Q2") (pin "C") (pinfunction "C_C") (pintype "passive"))
      (node (ref "Q22") (pin "C") (pinfunction "C_C") (pintype "passive"))
      (node (ref "Q27") (pin "C") (pinfunction "C_C") (pintype "passive"))
      (node (ref "Q28") (pin "C") (pinfunction "C_C") (pintype "passive"))
      (node (ref "Q3") (pin "C") (pinfunction "C_C") (pintype "passive"))
      (node (ref "Q8") (pin "E") (pinfunction "E_E") (pintype "passive"))
      (node (ref "R1") (pin "2") (pinfunction "2_2") (pintype "passive"))
      (node (ref "R11") (pin "2") (pinfunction "2_2") (pintype "passive"))
      (node (ref "R14") (pin "2") (pinfunction "2_2") (pintype "passive"))
      (node (ref "R16") (pin "2") (pinfunction "2_2") (pintype "passive"))
      (node (ref "R19") (pin "2") (pinfunction "2_2") (pintype "passive"))
      (node (ref "R35") (pin "2") (pinfunction "2_2") (pintype "passive"))
      (node (ref "R41") (pin "2") (pinfunction "2_2") (pintype "passive"))
      (node (ref "R53") (pin "2") (pinfunction "2_2") (pintype "passive"))
      (node (ref "R62") (pin "2") (pinfunction "2_2") (pintype "passive"))
      (node (ref "R69") (pin "2") (pinfunction "2_2") (pintype "passive"))
      (node (ref "R70") (pin "2") (pinfunction "2_2") (pintype "passive"))
      (node (ref "STRIP+") (pin "TP") (pinfunction "TP_TP") (pintype "input"))
      (node (ref "T1") (pin "A") (pinfunction "A_A") (pintype "passive"))
      (node (ref "TP14") (pin "TP") (pinfunction "TP_TP") (pintype "input"))
      (node (ref "VR6") (pin "E") (pinfunction "E_E") (pintype "passive"))
    )
    (net (code "2") (name "/~{GATE}") (class "Default")
      (node (ref "C22") (pin "1") (pinfunction "1_1") (pintype "passive"))
      (node (ref "D1") (pin "C") (pinfunction "C_C") (pintype "passive"))
      (node (ref "D10") (pin "C") (pinfunction "C_C") (pintype "passive"))
      (node (ref "D3") (pin "C") (pinfunction "C_C") (pintype "passive"))
      (node (ref "IC2") (pin "4") (pinfunction "O_4") (pintype "output"))
    )
    (net (code "3") (name "AGND") (class "Default")
      (node (ref "C29") (pin "+") (pinfunction "+_+") (pintype "passive"))
      (node (ref "IC1") (pin "2") (pinfunction "-IN_2") (pintype "input"))
      (node (ref "IC3") (pin "3") (pinfunction "+IN_3") (pintype "input"))
      (node (ref "IC3") (pin "5") (pinfunction "+IN_5") (pintype "input"))
      (node (ref "IC5") (pin "2") (pinfunction "-IN_2") (pintype "input"))
      (node (ref "IC5") (pin "5") (pinfunction "+IN_5") (pintype "input"))
      (node (ref "IC7") (pin "C") (pinfunction "C_C") (pintype "passive"))
      (node (ref "IC7") (pin "R") (pinfunction "R_R") (pintype "passive"))
      (node (ref "Q11") (pin "E") (pinfunction "E_E") (pintype "passive"))
      (node (ref "Q13") (pin "E") (pinfunction "E_E") (pintype "passive"))
      (node (ref "Q17") (pin "B") (pinfunction "B_B") (pintype "passive"))
      (node (ref "Q9") (pin "E") (pinfunction "E_E") (pintype "passive"))
      (node (ref "R28") (pin "1") (pinfunction "1_1") (pintype "passive"))
      (node (ref "R30") (pin "1") (pinfunction "1_1") (pintype "passive"))
      (node (ref "R46") (pin "1") (pinfunction "1_1") (pintype "passive"))
      (node (ref "R48") (pin "1") (pinfunction "1_1") (pintype "passive"))
      (node (ref "R53") (pin "1") (pinfunction "1_1") (pintype "passive"))
      (node (ref "R6") (pin "1") (pinfunction "1_1") (pintype "passive"))
      (node (ref "R72") (pin "1") (pinfunction "1_1") (pintype "passive"))
      (node (ref "STRIP-") (pin "TP") (pinfunction "TP_TP") (pintype "input"))
      (node (ref "TP16") (pin "TP") (pinfunction "TP_TP") (pintype "input"))
      (node (ref "VR5") (pin "A") (pinfunction "A_A") (pintype "passive"))
    )
    (net (code "4") (name "ENV") (class "Default")
      (node (ref "IC1") (pin "3") (pinfunction "+IN_3") (pintype "input"))
      (node (ref "Q22") (pin "E") (pinfunction "E_E") (pintype "passive"))
      (node (ref "SW1") (pin "6") (pinfunction "T2_6") (pintype "passive"))
      (node (ref "TP9") (pin "TP") (pinfunction "TP_TP") (pintype "input"))
      (node (ref "VR7") (pin "E") (pinfunction "E_E") (pintype "passive"))
    )
    (net (code "5") (name "GATE") (class "Default")
      (node (ref "D2") (pin "A") (pinfunction "A_A") (pintype "passive"))
      (node (ref "D6") (pin "A") (pinfunction "A_A") (pintype "passive"))
      (node (ref "IC2") (pin "1") (pinfunction "O_1") (pintype "output"))
      (node (ref "R20") (pin "1") (pinfunction "1_1") (pintype "passive"))
      (node (ref "R65") (pin "1") (pinfunction "1_1") (pintype "passive"))
      (node (ref "TP6") (pin "TP") (pinfunction "TP_TP") (pintype "input"))
    )
    (net (code "6") (name "GND") (class "Default")
      (node (ref "BAT-") (pin "TP") (pinfunction "TP_TP") (pintype "input"))
      (node (ref "C1") (pin "2") (pinfunction "2_2") (pintype "passive"))
      (node (ref "C16") (pin "2") (pinfunction "2_2") (pintype "passive"))
      (node (ref "C2") (pin "2") (pinfunction "2_2") (pintype "passive"))
      (node (ref "C20") (pin "-") (pinfunction "-_-") (pintype "passive"))
      (node (ref "C23") (pin "-") (pinfunction "-_-") (pintype "passive"))
      (node (ref "C25") (pin "-") (pinfunction "-_-") (pintype "passive"))
      (node (ref "C26") (pin "-") (pinfunction "-_-") (pintype "passive"))
      (node (ref "C27") (pin "2") (pinfunction "2_2") (pintype "passive"))
      (node (ref "C28") (pin "-") (pinfunction "-_-") (pintype "passive"))
      (node (ref "C29") (pin "-") (pinfunction "-_-") (pintype "passive"))
      (node (ref "C3") (pin "2") (pinfunction "2_2") (pintype "passive"))
      (node (ref "C4") (pin "2") (pinfunction "2_2") (pintype "passive"))
      (node (ref "C6") (pin "-") (pinfunction "-_-") (pintype "passive"))
      (node (ref "IC1") (pin "4") (pinfunction "V-_4") (pintype "power_in"))
      (node (ref "IC2") (pin "7") (pinfunction "GND_7") (pintype "power_in"))
      (node (ref "IC3") (pin "4") (pinfunction "V-_4") (pintype "power_in"))
      (node (ref "IC4") (pin "2") (pinfunction "-IN_2") (pintype "input"))
      (node (ref "IC4") (pin "4") (pinfunction "GND_4") (pintype "power_in"))
      (node (ref "IC5") (pin "4") (pinfunction "V-_4") (pintype "power_in"))
      (node (ref "IC6") (pin "1") (pinfunction "GND_1") (pintype "power_in"))
      (node (ref "IC7") (pin "A") (pinfunction "A_A") (pintype "passive"))
      (node (ref "J1") (pin "3") (pinfunction "1_3") (pintype "passive"))
      (node (ref "J2") (pin "3") (pinfunction "1_3") (pintype "passive"))
      (node (ref "LED1") (pin "K") (pinfunction "C_K") (pintype "passive"))
      (node (ref "Q12") (pin "E") (pinfunction "E_E") (pintype "passive"))
      (node (ref "Q23") (pin "E") (pinfunction "E_E") (pintype "passive"))
      (node (ref "Q24") (pin "C") (pinfunction "C_C") (pintype "passive"))
      (node (ref "R23") (pin "1") (pinfunction "1_1") (pintype "passive"))
      (node (ref "R36") (pin "1") (pinfunction "1_1") (pintype "passive"))
      (node (ref "R37") (pin "1") (pinfunction "1_1") (pintype "passive"))
      (node (ref "R38") (pin "1") (pinfunction "1_1") (pintype "passive"))
      (node (ref "R39") (pin "1") (pinfunction "1_1") (pintype "passive"))
      (node (ref "R40") (pin "1") (pinfunction "1_1") (pintype "passive"))
      (node (ref "R42") (pin "1") (pinfunction "1_1") (pintype "passive"))
      (node (ref "R51") (pin "1") (pinfunction "1_1") (pintype "passive"))
      (node (ref "R55") (pin "1") (pinfunction "1_1") (pintype "passive"))
      (node (ref "R58") (pin "1") (pinfunction "1_1") (pintype "passive"))
      (node (ref "R68") (pin "1") (pinfunction "1_1") (pintype "passive"))
      (node (ref "R7") (pin "1") (pinfunction "1_1") (pintype "passive"))
      (node (ref "R71") (pin "1") (pinfunction "1_1") (pintype "passive"))
      (node (ref "R73") (pin "1") (pinfunction "1_1") (pintype "passive"))
      (node (ref "R8") (pin "1") (pinfunction "1_1") (pintype "passive"))
      (node (ref "SW1") (pin "4") (pinfunction "T3_4") (pintype "passive"))
      (node (ref "T1") (pin "E") (pinfunction "E_E") (pintype "passive"))
      (node (ref "TP15") (pin "TP") (pinfunction "TP_TP") (pintype "input"))
      (node (ref "VR6") (pin "A") (pinfunction "A_A") (pintype "passive"))
      (node (ref "VR7") (pin "A") (pinfunction "A_A") (pintype "passive"))
      (node (ref "X2") (pin "2") (pinfunction "S_2") (pintype "passive"))
    )
    (net (code "7") (name "GND1") (class "Default")
      (node (ref "C23") (pin "+") (pinfunction "+_+") (pintype "passive"))
      (node (ref "Q25") (pin "E") (pinfunction "E_E") (pintype "passive"))
      (node (ref "R33") (pin "1") (pinfunction "1_1") (pintype "passive"))
      (node (ref "R34") (pin "1") (pinfunction "1_1") (pintype "passive"))
      (node (ref "R35") (pin "1") (pinfunction "1_1") (pintype "passive"))
      (node (ref "R39") (pin "2") (pinfunction "2_2") (pintype "passive"))
      (node (ref "TP8") (pin "TP") (pinfunction "TP_TP") (pintype "input"))
    )
    (net (code "8") (name "LFO") (class "Default")
      (node (ref "FINGERPAD2") (pin "A0") (pinfunction "A0_A0") (pintype "passive"))
      (node (ref "FINGERPAD2") (pin "A1") (pinfunction "A1_A1") (pintype "passive"))
      (node (ref "SW2") (pin "2") (pinfunction "P_2") (pintype "passive"))
      (node (ref "VR5") (pin "E") (pinfunction "E_E") (pintype "passive"))
    )
    (net (code "9") (name "Net-(C6-Pad+)") (class "Default")
      (node (ref "C6") (pin "+") (pinfunction "+_+") (pintype "passive"))
      (node (ref "Q1") (pin "B") (pinfunction "B_B") (pintype "passive"))
      (node (ref "Q2") (pin "B") (pinfunction "B_B") (pintype "passive"))
      (node (ref "R1") (pin "1") (pinfunction "1_1") (pintype "passive"))
    )
    (net (code "10") (name "Net-(C7-Pad1)") (class "Default")
      (node (ref "C7") (pin "1") (pinfunction "1_1") (pintype "passive"))
      (node (ref "C8") (pin "1") (pinfunction "1_1") (pintype "passive"))
      (node (ref "Q1") (pin "E") (pinfunction "E_E") (pintype "passive"))
      (node (ref "Q4") (pin "B") (pinfunction "B_B") (pintype "passive"))
      (node (ref "Q4") (pin "C") (pinfunction "C_C") (pintype "passive"))
      (node (ref "TP1") (pin "TP") (pinfunction "TP_TP") (pintype "input"))
    )
    (net (code "11") (name "Net-(C7-Pad2)") (class "Default")
      (node (ref "C7") (pin "2") (pinfunction "2_2") (pintype "passive"))
      (node (ref "R3") (pin "1") (pinfunction "1_1") (pintype "passive"))
    )
    (net (code "12") (name "Net-(C8-Pad2)") (class "Default")
      (node (ref "C8") (pin "2") (pinfunction "2_2") (pintype "passive"))
      (node (ref "C9") (pin "2") (pinfunction "2_2") (pintype "passive"))
      (node (ref "Q2") (pin "E") (pinfunction "E_E") (pintype "passive"))
      (node (ref "Q5") (pin "B") (pinfunction "B_B") (pintype "passive"))
      (node (ref "Q5") (pin "C") (pinfunction "C_C") (pintype "passive"))
      (node (ref "TP4") (pin "TP") (pinfunction "TP_TP") (pintype "input"))
    )
    (net (code "13") (name "Net-(C9-Pad1)") (class "Default")
      (node (ref "C9") (pin "1") (pinfunction "1_1") (pintype "passive"))
      (node (ref "R4") (pin "1") (pinfunction "1_1") (pintype "passive"))
    )
    (net (code "14") (name "Net-(C10-Pad+)") (class "Default")
      (node (ref "C10") (pin "+") (pinfunction "+_+") (pintype "passive"))
      (node (ref "Q3") (pin "E") (pinfunction "E_E") (pintype "passive"))
      (node (ref "R7") (pin "2") (pinfunction "2_2") (pintype "passive"))
    )
    (net (code "15") (name "Net-(C11-Pad1)") (class "Default")
      (node (ref "C11") (pin "1") (pinfunction "1_1") (pintype "passive"))
      (node (ref "Q4") (pin "E") (pinfunction "E_E") (pintype "passive"))
      (node (ref "Q6") (pin "B") (pinfunction "B_B") (pintype "passive"))
      (node (ref "Q6") (pin "C") (pinfunction "C_C") (pintype "passive"))
    )
    (net (code "16") (name "Net-(C11-Pad2)") (class "Default")
      (node (ref "C11") (pin "2") (pinfunction "2_2") (pintype "passive"))
      (node (ref "Q5") (pin "E") (pinfunction "E_E") (pintype "passive"))
      (node (ref "Q7") (pin "B") (pinfunction "B_B") (pintype "passive"))
      (node (ref "Q7") (pin "C") (pinfunction "C_C") (pintype "passive"))
    )
    (net (code "17") (name "Net-(C12-Pad1)") (class "Default")
      (node (ref "C12") (pin "1") (pinfunction "1_1") (pintype "passive"))
      (node (ref "Q14") (pin "B") (pinfunction "B_B") (pintype "passive"))
      (node (ref "Q14") (pin "C") (pinfunction "C_C") (pintype "passive"))
      (node (ref "Q6") (pin "E") (pinfunction "E_E") (pintype "passive"))
    )
    (net (code "18") (name "Net-(C12-Pad2)") (class "Default")
      (node (ref "C12") (pin "2") (pinfunction "2_2") (pintype "passive"))
      (node (ref "Q15") (pin "B") (pinfunction "B_B") (pintype "passive"))
      (node (ref "Q15") (pin "C") (pinfunction "C_C") (pintype "passive"))
      (node (ref "Q7") (pin "E") (pinfunction "E_E") (pintype "passive"))
    )
    (net (code "19") (name "Net-(C13-Pad2)") (class "Default")
      (node (ref "C13") (pin "2") (pinfunction "2_2") (pintype "passive"))
      (node (ref "Q17") (pin "C") (pinfunction "C_C") (pintype "passive"))
      (node (ref "Q8") (pin "C") (pinfunction "C_C") (pintype "passive"))
      (node (ref "R75") (pin "2") (pinfunction "2_2") (pintype "passive"))
    )
    (net (code "20") (name "Net-(C14-Pad+)") (class "Default")
      (node (ref "C14") (pin "+") (pinfunction "+_+") (pintype "passive"))
      (node (ref "IC4") (pin "8") (pinfunction "GAIN_8") (pintype "passive"))
    )
    (net (code "21") (name "Net-(C14-Pad-)") (class "Default")
      (node (ref "C14") (pin "-") (pinfunction "-_-") (pintype "passive"))
      (node (ref "R12") (pin "2") (pinfunction "2_2") (pintype "passive"))
    )
    (net (code "22") (name "Net-(C15-Pad+)") (class "Default")
      (node (ref "C15") (pin "+") (pinfunction "+_+") (pintype "passive"))
      (node (ref "Q10") (pin "E") (pinfunction "E_E") (pintype "passive"))
      (node (ref "R23") (pin "2") (pinfunction "2_2") (pintype "passive"))
    )
    (net (code "23") (name "Net-(C15-Pad-)") (class "Default")
      (node (ref "C15") (pin "-") (pinfunction "-_-") (pintype "passive"))
      (node (ref "R27") (pin "2") (pinfunction "2_2") (pintype "passive"))
      (node (ref "TP5") (pin "TP") (pinfunction "TP_TP") (pintype "input"))
    )
    (net (code "24") (name "Net-(C17-Pad1)") (class "Default")
      (node (ref "C17") (pin "1") (pinfunction "1_1") (pintype "passive"))
      (node (ref "Q14") (pin "E") (pinfunction "E_E") (pintype "passive"))
      (node (ref "Q20") (pin "C") (pinfunction "C_C") (pintype "passive"))
    )
    (net (code "25") (name "Net-(C17-Pad2)") (class "Default")
      (node (ref "C17") (pin "2") (pinfunction "2_2") (pintype "passive"))
      (node (ref "Q15") (pin "E") (pinfunction "E_E") (pintype "passive"))
      (node (ref "Q21") (pin "C") (pinfunction "C_C") (pintype "passive"))
    )
    (net (code "26") (name "Net-(C18-Pad2)") (class "Default")
      (node (ref "C18") (pin "2") (pinfunction "2_2") (pintype "passive"))
      (node (ref "R36") (pin "2") (pinfunction "2_2") (pintype "passive"))
    )
    (net (code "27") (name "Net-(C19-Pad2)") (class "Default")
      (node (ref "C19") (pin "2") (pinfunction "2_2") (pintype "passive"))
      (node (ref "R31") (pin "1") (pinfunction "1_1") (pintype "passive"))
    )
    (net (code "28") (name "Net-(C25-Pad+)") (class "Default")
      (node (ref "C25") (pin "+") (pinfunction "+_+") (pintype "passive"))
      (node (ref "Q22") (pin "B") (pinfunction "B_B") (pintype "passive"))
      (node (ref "VR2") (pin "E") (pinfunction "E_E") (pintype "passive"))
      (node (ref "VR2") (pin "S") (pinfunction "S_S") (pintype "passive"))
      (node (ref "VR3") (pin "E") (pinfunction "E_E") (pintype "passive"))
      (node (ref "VR3") (pin "S") (pinfunction "S_S") (pintype "passive"))
    )
    (net (code "29") (name "Net-(C30-Pad2)") (class "Default")
      (node (ref "C30") (pin "2") (pinfunction "2_2") (pintype "passive"))
      (node (ref "R56") (pin "1") (pinfunction "1_1") (pintype "passive"))
    )
    (net (code "30") (name "Net-(C31-Pad2)") (class "Default")
      (node (ref "C31") (pin "2") (pinfunction "2_2") (pintype "passive"))
      (node (ref "Q26") (pin "B") (pinfunction "B_B") (pintype "passive"))
      (node (ref "R68") (pin "2") (pinfunction "2_2") (pintype "passive"))
      (node (ref "R69") (pin "1") (pinfunction "1_1") (pintype "passive"))
    )
    (net (code "31") (name "Net-(D1-PadA)") (class "Default")
      (node (ref "D1") (pin "A") (pinfunction "A_A") (pintype "passive"))
      (node (ref "Q13") (pin "B") (pinfunction "B_B") (pintype "passive"))
      (node (ref "R18") (pin "1") (pinfunction "1_1") (pintype "passive"))
      (node (ref "R26") (pin "2") (pinfunction "2_2") (pintype "passive"))
    )
    (net (code "32") (name "Net-(D4-PadA)") (class "Default")
      (node (ref "D4") (pin "A") (pinfunction "A_A") (pintype "passive"))
      (node (ref "R77") (pin "1") (pinfunction "1_1") (pintype "passive"))
    )
    (net (code "33") (name "Net-(D5-PadC)") (class "Default")
      (node (ref "D5") (pin "C") (pinfunction "C_C") (pintype "passive"))
      (node (ref "R64") (pin "1") (pinfunction "1_1") (pintype "passive"))
    )
    (net (code "34") (name "Net-(D7-PadA)") (class "Default")
      (node (ref "D7") (pin "A") (pinfunction "A_A") (pintype "passive"))
      (node (ref "Q28") (pin "E") (pinfunction "E_E") (pintype "passive"))
    )
    (net (code "35") (name "Net-(D7-PadC)") (class "Default")
      (node (ref "D7") (pin "C") (pinfunction "C_C") (pintype "passive"))
      (node (ref "D8") (pin "A") (pinfunction "A_A") (pintype "passive"))
    )
    (net (code "36") (name "Net-(D8-PadC)") (class "Default")
      (node (ref "D8") (pin "C") (pinfunction "C_C") (pintype "passive"))
      (node (ref "D9") (pin "A") (pinfunction "A_A") (pintype "passive"))
    )
    (net (code "37") (name "Net-(D9-PadC)") (class "Default")
      (node (ref "D9") (pin "C") (pinfunction "C_C") (pintype "passive"))
      (node (ref "R73") (pin "2") (pinfunction "2_2") (pintype "passive"))
      (node (ref "R74") (pin "1") (pinfunction "1_1") (pintype "passive"))
    )
    (net (code "38") (name "Net-(D10-PadA)") (class "Default")
      (node (ref "D10") (pin "A") (pinfunction "A_A") (pintype "passive"))
      (node (ref "R76") (pin "1") (pinfunction "1_1") (pintype "passive"))
    )
    (net (code "39") (name "Net-(FINGERPAD2-PadB0)") (class "Default")
      (node (ref "FINGERPAD2") (pin "B0") (pinfunction "B0_B0") (pintype "passive"))
      (node (ref "FINGERPAD2") (pin "B1") (pinfunction "B1_B1") (pintype "passive"))
      (node (ref "R63") (pin "1") (pinfunction "1_1") (pintype "passive"))
    )
    (net (code "40") (name "Net-(IC1A-OUT)") (class "Default")
      (node (ref "IC1") (pin "1") (pinfunction "OUT_1") (pintype "output"))
      (node (ref "R47") (pin "2") (pinfunction "2_2") (pintype "passive"))
    )
    (net (code "41") (name "Net-(IC1B-+IN)") (class "Default")
      (node (ref "IC1") (pin "5") (pinfunction "+IN_5") (pintype "input"))
      (node (ref "R4") (pin "2") (pinfunction "2_2") (pintype "passive"))
      (node (ref "R6") (pin "2") (pinfunction "2_2") (pintype "passive"))
    )
    (net (code "42") (name "Net-(IC1B--IN)") (class "Default")
      (node (ref "IC1") (pin "6") (pinfunction "-IN_6") (pintype "input"))
      (node (ref "R2") (pin "1") (pinfunction "1_1") (pintype "passive"))
      (node (ref "R3") (pin "2") (pinfunction "2_2") (pintype "passive"))
    )
    (net (code "43") (name "Net-(IC2A-I0)") (class "Default")
      (node (ref "IC2") (pin "2") (pinfunction "I0_2") (pintype "input"))
      (node (ref "IC2") (pin "3") (pinfunction "I1_3") (pintype "input"))
      (node (ref "Q12") (pin "C") (pinfunction "C_C") (pintype "passive"))
      (node (ref "R13") (pin "2") (pinfunction "2_2") (pintype "passive"))
      (node (ref "R14") (pin "1") (pinfunction "1_1") (pintype "passive"))
    )
    (net (code "44") (name "Net-(IC2B-I0)") (class "Default")
      (node (ref "C16") (pin "1") (pinfunction "1_1") (pintype "passive"))
      (node (ref "D2") (pin "C") (pinfunction "C_C") (pintype "passive"))
      (node (ref "IC2") (pin "5") (pinfunction "I0_5") (pintype "input"))
      (node (ref "IC2") (pin "6") (pinfunction "I1_6") (pintype "input"))
      (node (ref "R20") (pin "2") (pinfunction "2_2") (pintype "passive"))
    )
    (net (code "45") (name "Net-(IC2C-I0)") (class "Default")
      (node (ref "C22") (pin "2") (pinfunction "2_2") (pintype "passive"))
      (node (ref "IC2") (pin "8") (pinfunction "I0_8") (pintype "input"))
      (node (ref "R40") (pin "2") (pinfunction "2_2") (pintype "passive"))
    )
    (net (code "46") (name "Net-(IC2C-I1)") (class "Default")
      (node (ref "D4") (pin "C") (pinfunction "C_C") (pintype "passive"))
      (node (ref "D5") (pin "A") (pinfunction "A_A") (pintype "passive"))
      (node (ref "IC2") (pin "13") (pinfunction "O_13") (pintype "output"))
      (node (ref "IC2") (pin "9") (pinfunction "I1_9") (pintype "input"))
      (node (ref "TP11") (pin "TP") (pinfunction "TP_TP") (pintype "input"))
    )
    (net (code "47") (name "Net-(IC2C-O)") (class "Default")
      (node (ref "IC2") (pin "10") (pinfunction "O_10") (pintype "output"))
      (node (ref "IC2") (pin "11") (pinfunction "I0_11") (pintype "input"))
    )
    (net (code "48") (name "Net-(IC2D-I1)") (class "Default")
      (node (ref "D6") (pin "C") (pinfunction "C_C") (pintype "passive"))
      (node (ref "IC2") (pin "12") (pinfunction "I1_12") (pintype "input"))
      (node (ref "R47") (pin "1") (pinfunction "1_1") (pintype "passive"))
    )
    (net (code "49") (name "Net-(IC3A--IN)") (class "Default")
      (node (ref "IC3") (pin "2") (pinfunction "-IN_2") (pintype "input"))
      (node (ref "R10") (pin "2") (pinfunction "2_2") (pintype "passive"))
      (node (ref "R21") (pin "1") (pinfunction "1_1") (pintype "passive"))
      (node (ref "R5") (pin "2") (pinfunction "2_2") (pintype "passive"))
      (node (ref "R59") (pin "2") (pinfunction "2_2") (pintype "passive"))
      (node (ref "R61") (pin "2") (pinfunction "2_2") (pintype "passive"))
      (node (ref "R9") (pin "2") (pinfunction "2_2") (pintype "passive"))
    )
    (net (code "50") (name "Net-(IC3A-OUT)") (class "Default")
      (node (ref "IC3") (pin "1") (pinfunction "OUT_1") (pintype "output"))
      (node (ref "R21") (pin "2") (pinfunction "2_2") (pintype "passive"))
      (node (ref "R25") (pin "1") (pinfunction "1_1") (pintype "passive"))
    )
    (net (code "51") (name "Net-(IC3B--IN)") (class "Default")
      (node (ref "C21") (pin "1") (pinfunction "1_1") (pintype "passive"))
      (node (ref "IC3") (pin "6") (pinfunction "-IN_6") (pintype "input"))
      (node (ref "Q16") (pin "C") (pinfunction "C_C") (pintype "passive"))
      (node (ref "R19") (pin "1") (pinfunction "1_1") (pintype "passive"))
    )
    (net (code "52") (name "Net-(IC3B-OUT)") (class "Default")
      (node (ref "C21") (pin "2") (pinfunction "2_2") (pintype "passive"))
      (node (ref "IC3") (pin "7") (pinfunction "OUT_7") (pintype "output"))
      (node (ref "R32") (pin "1") (pinfunction "1_1") (pintype "passive"))
    )
    (net (code "53") (name "Net-(IC4-+IN)") (class "Default")
      (node (ref "IC4") (pin "3") (pinfunction "+IN_3") (pintype "input"))
      (node (ref "R24") (pin "2") (pinfunction "2_2") (pintype "passive"))
    )
    (net (code "54") (name "Net-(IC4-BYPASS)") (class "Default")
      (node (ref "C20") (pin "+") (pinfunction "+_+") (pintype "passive"))
      (node (ref "IC4") (pin "7") (pinfunction "BYPASS_7") (pintype "passive"))
    )
    (net (code "55") (name "Net-(IC4-GAIN-Pad1)") (class "Default")
      (node (ref "IC4") (pin "1") (pinfunction "GAIN_1") (pintype "passive"))
      (node (ref "R12") (pin "1") (pinfunction "1_1") (pintype "passive"))
    )
    (net (code "56") (name "Net-(IC4-OUT)") (class "Default")
      (node (ref "C18") (pin "1") (pinfunction "1_1") (pintype "passive"))
      (node (ref "C5") (pin "+") (pinfunction "+_+") (pintype "passive"))
      (node (ref "IC4") (pin "5") (pinfunction "OUT_5") (pintype "output"))
    )
    (net (code "57") (name "Net-(IC5A-+IN)") (class "Default")
      (node (ref "D3") (pin "A") (pinfunction "A_A") (pintype "passive"))
      (node (ref "IC5") (pin "3") (pinfunction "+IN_3") (pintype "input"))
      (node (ref "R44") (pin "1") (pinfunction "1_1") (pintype "passive"))
      (node (ref "R45") (pin "2") (pinfunction "2_2") (pintype "passive"))
    )
    (net (code "58") (name "Net-(IC5B--IN)") (class "Default")
      (node (ref "C24") (pin "1") (pinfunction "1_1") (pintype "passive"))
      (node (ref "IC5") (pin "6") (pinfunction "-IN_6") (pintype "input"))
      (node (ref "R43") (pin "1") (pinfunction "1_1") (pintype "passive"))
    )
    (net (code "59") (name "Net-(J1-2)") (class "Default")
      (node (ref "C10") (pin "-") (pinfunction "-_-") (pintype "passive"))
      (node (ref "J1") (pin "1") (pinfunction "2_1") (pintype "passive"))
      (node (ref "R8") (pin "2") (pinfunction "2_2") (pintype "passive"))
    )
    (net (code "60") (name "Net-(J1-3)") (class "Default")
      (node (ref "J1") (pin "2") (pinfunction "3_2") (pintype "passive"))
      (node (ref "R22") (pin "1") (pinfunction "1_1") (pintype "passive"))
    )
    (net (code "61") (name "Net-(J2-2)") (class "Default")
      (node (ref "C30") (pin "1") (pinfunction "1_1") (pintype "passive"))
      (node (ref "J2") (pin "1") (pinfunction "2_1") (pintype "passive"))
    )
    (net (code "62") (name "Net-(LED1-PadA)") (class "Default")
      (node (ref "LED1") (pin "A") (pinfunction "A_A") (pintype "passive"))
      (node (ref "R60") (pin "1") (pinfunction "1_1") (pintype "passive"))
    )
    (net (code "63") (name "Net-(PAD1-PadA0)") (class "Default")
      (node (ref "PAD1") (pin "A0") (pinfunction "A0_A0") (pintype "passive"))
      (node (ref "PAD1") (pin "A1") (pinfunction "A1_A1") (pintype "passive"))
      (node (ref "R62") (pin "1") (pinfunction "1_1") (pintype "passive"))
    )
    (net (code "64") (name "Net-(PAD1-PadB0)") (class "Default")
      (node (ref "PAD1") (pin "B0") (pinfunction "B0_B0") (pintype "passive"))
      (node (ref "PAD1") (pin "B1") (pinfunction "B1_B1") (pintype "passive"))
      (node (ref "R50") (pin "1") (pinfunction "1_1") (pintype "passive"))
      (node (ref "R51") (pin "2") (pinfunction "2_2") (pintype "passive"))
    )
    (net (code "65") (name "Net-(Q8-PadB)") (class "Default")
      (node (ref "Q8") (pin "B") (pinfunction "B_B") (pintype "passive"))
      (node (ref "R16") (pin "1") (pinfunction "1_1") (pintype "passive"))
      (node (ref "R17") (pin "2") (pinfunction "2_2") (pintype "passive"))
    )
    (net (code "66") (name "Net-(Q9-PadC)") (class "Default")
      (node (ref "Q9") (pin "C") (pinfunction "C_C") (pintype "passive"))
      (node (ref "R17") (pin "1") (pinfunction "1_1") (pintype "passive"))
      (node (ref "R18") (pin "2") (pinfunction "2_2") (pintype "passive"))
    )
    (net (code "67") (name "Net-(Q10-PadB)") (class "Default")
      (node (ref "Q10") (pin "B") (pinfunction "B_B") (pintype "passive"))
      (node (ref "VR1") (pin "S") (pinfunction "S_S") (pintype "passive"))
    )
    (net (code "68") (name "Net-(Q11-PadB)") (class "Default")
      (node (ref "Q11") (pin "B") (pinfunction "B_B") (pintype "passive"))
      (node (ref "R15") (pin "2") (pinfunction "2_2") (pintype "passive"))
    )
    (net (code "69") (name "Net-(Q11-PadC)") (class "Default")
      (node (ref "Q11") (pin "C") (pinfunction "C_C") (pintype "passive"))
      (node (ref "R54") (pin "1") (pinfunction "1_1") (pintype "passive"))
    )
    (net (code "70") (name "Net-(Q12-PadB)") (class "Default")
      (node (ref "Q12") (pin "B") (pinfunction "B_B") (pintype "passive"))
      (node (ref "R54") (pin "2") (pinfunction "2_2") (pintype "passive"))
    )
    (net (code "71") (name "Net-(Q13-PadC)") (class "Default")
      (node (ref "Q13") (pin "C") (pinfunction "C_C") (pintype "passive"))
      (node (ref "Q9") (pin "B") (pinfunction "B_B") (pintype "passive"))
      (node (ref "R11") (pin "1") (pinfunction "1_1") (pintype "passive"))
    )
    (net (code "72") (name "Net-(Q16-PadB)") (class "Default")
      (node (ref "Q16") (pin "B") (pinfunction "B_B") (pintype "passive"))
      (node (ref "R25") (pin "2") (pinfunction "2_2") (pintype "passive"))
      (node (ref "R30") (pin "2") (pinfunction "2_2") (pintype "passive"))
    )
    (net (code "73") (name "Net-(Q16-PadE)") (class "Default")
      (node (ref "Q16") (pin "E") (pinfunction "E_E") (pintype "passive"))
      (node (ref "Q17") (pin "E") (pinfunction "E_E") (pintype "passive"))
      (node (ref "R32") (pin "2") (pinfunction "2_2") (pintype "passive"))
    )
    (net (code "74") (name "Net-(Q18-PadB)") (class "Default")
      (node (ref "Q18") (pin "B") (pinfunction "B_B") (pintype "passive"))
      (node (ref "R75") (pin "1") (pinfunction "1_1") (pintype "passive"))
      (node (ref "R76") (pin "2") (pinfunction "2_2") (pintype "passive"))
    )
    (net (code "75") (name "Net-(Q18-PadE)") (class "Default")
      (node (ref "Q18") (pin "E") (pinfunction "E_E") (pintype "passive"))
      (node (ref "Q19") (pin "B") (pinfunction "B_B") (pintype "passive"))
    )
    (net (code "76") (name "Net-(Q20-PadB)") (class "Default")
      (node (ref "Q20") (pin "B") (pinfunction "B_B") (pintype "passive"))
      (node (ref "R31") (pin "2") (pinfunction "2_2") (pintype "passive"))
      (node (ref "R33") (pin "2") (pinfunction "2_2") (pintype "passive"))
      (node (ref "R56") (pin "2") (pinfunction "2_2") (pintype "passive"))
    )
    (net (code "77") (name "Net-(Q20-PadE)") (class "Default")
      (node (ref "Q20") (pin "E") (pinfunction "E_E") (pintype "passive"))
      (node (ref "Q21") (pin "E") (pinfunction "E_E") (pintype "passive"))
      (node (ref "Q23") (pin "C") (pinfunction "C_C") (pintype "passive"))
    )
    (net (code "78") (name "Net-(Q21-PadB)") (class "Default")
      (node (ref "Q21") (pin "B") (pinfunction "B_B") (pintype "passive"))
      (node (ref "R27") (pin "1") (pinfunction "1_1") (pintype "passive"))
      (node (ref "R34") (pin "2") (pinfunction "2_2") (pintype "passive"))
      (node (ref "R67") (pin "2") (pinfunction "2_2") (pintype "passive"))
    )
    (net (code "79") (name "Net-(Q23-PadB)") (class "Default")
      (node (ref "Q23") (pin "B") (pinfunction "B_B") (pintype "passive"))
      (node (ref "Q24") (pin "E") (pinfunction "E_E") (pintype "passive"))
      (node (ref "R41") (pin "1") (pinfunction "1_1") (pintype "passive"))
    )
    (net (code "80") (name "Net-(Q24-PadB)") (class "Default")
      (node (ref "Q24") (pin "B") (pinfunction "B_B") (pintype "passive"))
      (node (ref "R42") (pin "2") (pinfunction "2_2") (pintype "passive"))
      (node (ref "R49") (pin "2") (pinfunction "2_2") (pintype "passive"))
      (node (ref "R50") (pin "2") (pinfunction "2_2") (pintype "passive"))
      (node (ref "R52") (pin "2") (pinfunction "2_2") (pintype "passive"))
      (node (ref "R74") (pin "2") (pinfunction "2_2") (pintype "passive"))
    )
    (net (code "81") (name "Net-(Q25-PadB)") (class "Default")
      (node (ref "Q25") (pin "B") (pinfunction "B_B") (pintype "passive"))
      (node (ref "R65") (pin "2") (pinfunction "2_2") (pintype "passive"))
    )
    (net (code "82") (name "Net-(Q25-PadC)") (class "Default")
      (node (ref "Q25") (pin "C") (pinfunction "C_C") (pintype "passive"))
      (node (ref "R67") (pin "1") (pinfunction "1_1") (pintype "passive"))
    )
    (net (code "83") (name "Net-(Q26-PadC)") (class "Default")
      (node (ref "Q26") (pin "C") (pinfunction "C_C") (pintype "passive"))
      (node (ref "Q3") (pin "B") (pinfunction "B_B") (pintype "passive"))
      (node (ref "R70") (pin "1") (pinfunction "1_1") (pintype "passive"))
    )
    (net (code "84") (name "Net-(Q26-PadE)") (class "Default")
      (node (ref "Q26") (pin "E") (pinfunction "E_E") (pintype "passive"))
      (node (ref "R71") (pin "2") (pinfunction "2_2") (pintype "passive"))
    )
    (net (code "85") (name "Net-(Q27-PadE)") (class "Default")
      (node (ref "Q27") (pin "E") (pinfunction "E_E") (pintype "passive"))
      (node (ref "Q28") (pin "B") (pinfunction "B_B") (pintype "passive"))
    )
    (net (code "86") (name "Net-(R10-Pad1)") (class "Default")
      (node (ref "R10") (pin "1") (pinfunction "1_1") (pintype "passive"))
      (node (ref "T1") (pin "S") (pinfunction "S_S") (pintype "passive"))
    )
    (net (code "87") (name "Net-(R22-Pad2)") (class "Default")
      (node (ref "R22") (pin "2") (pinfunction "2_2") (pintype "passive"))
      (node (ref "R24") (pin "1") (pinfunction "1_1") (pintype "passive"))
      (node (ref "R38") (pin "2") (pinfunction "2_2") (pintype "passive"))
    )
    (net (code "88") (name "Net-(R28-Pad2)") (class "Default")
      (node (ref "R28") (pin "2") (pinfunction "2_2") (pintype "passive"))
      (node (ref "VR1") (pin "A") (pinfunction "A_A") (pintype "passive"))
    )
    (net (code "89") (name "Net-(R43-Pad2)") (class "Default")
      (node (ref "R43") (pin "2") (pinfunction "2_2") (pintype "passive"))
      (node (ref "R66") (pin "2") (pinfunction "2_2") (pintype "passive"))
      (node (ref "VR4") (pin "S") (pinfunction "S_S") (pintype "passive"))
    )
    (net (code "90") (name "Net-(R46-Pad2)") (class "Default")
      (node (ref "R46") (pin "2") (pinfunction "2_2") (pintype "passive"))
      (node (ref "R66") (pin "1") (pinfunction "1_1") (pintype "passive"))
      (node (ref "VR4") (pin "A") (pinfunction "A_A") (pintype "passive"))
    )
    (net (code "91") (name "Net-(R48-Pad2)") (class "Default")
      (node (ref "R48") (pin "2") (pinfunction "2_2") (pintype "passive"))
      (node (ref "R63") (pin "2") (pinfunction "2_2") (pintype "passive"))
      (node (ref "R9") (pin "1") (pinfunction "1_1") (pintype "passive"))
    )
    (net (code "92") (name "Net-(R49-Pad1)") (class "Default")
      (node (ref "R49") (pin "1") (pinfunction "1_1") (pintype "passive"))
      (node (ref "VR6") (pin "S") (pinfunction "S_S") (pintype "passive"))
    )
    (net (code "93") (name "Net-(R52-Pad1)") (class "Default")
      (node (ref "R52") (pin "1") (pinfunction "1_1") (pintype "passive"))
      (node (ref "R57") (pin "2") (pinfunction "2_2") (pintype "passive"))
      (node (ref "R58") (pin "2") (pinfunction "2_2") (pintype "passive"))
    )
    (net (code "94") (name "Net-(R59-Pad1)") (class "Default")
      (node (ref "R59") (pin "1") (pinfunction "1_1") (pintype "passive"))
      (node (ref "VR7") (pin "S") (pinfunction "S_S") (pintype "passive"))
    )
    (net (code "95") (name "Net-(R61-Pad1)") (class "Default")
      (node (ref "R61") (pin "1") (pinfunction "1_1") (pintype "passive"))
      (node (ref "R72") (pin "2") (pinfunction "2_2") (pintype "passive"))
      (node (ref "VR5") (pin "S") (pinfunction "S_S") (pintype "passive"))
    )
    (net (code "96") (name "Net-(R64-Pad2)") (class "Default")
      (node (ref "R64") (pin "2") (pinfunction "2_2") (pintype "passive"))
      (node (ref "VR3") (pin "A") (pinfunction "A_A") (pintype "passive"))
    )
    (net (code "97") (name "Net-(R77-Pad2)") (class "Default")
      (node (ref "R77") (pin "2") (pinfunction "2_2") (pintype "passive"))
      (node (ref "VR2") (pin "A") (pinfunction "A_A") (pintype "passive"))
    )
    (net (code "98") (name "Net-(SW1A-P1)") (class "Default")
      (node (ref "R57") (pin "1") (pinfunction "1_1") (pintype "passive"))
      (node (ref "SW1") (pin "5") (pinfunction "P1_5") (pintype "passive"))
    )
    (net (code "99") (name "Net-(SW1B-P1)") (class "Default")
      (node (ref "BAT+") (pin "TP") (pinfunction "TP_TP") (pintype "input"))
      (node (ref "SW1") (pin "1") (pinfunction "P1_1") (pintype "passive"))
    )
    (net (code "100") (name "Net-(X2A-S)") (class "Default")
      (node (ref "C5") (pin "-") (pinfunction "-_-") (pintype "passive"))
      (node (ref "X2") (pin "1") (pinfunction "S_1") (pintype "passive"))
    )
    (net (code "101") (name "SQR") (class "Default")
      (node (ref "IC5") (pin "1") (pinfunction "OUT_1") (pintype "output"))
      (node (ref "R44") (pin "2") (pinfunction "2_2") (pintype "passive"))
      (node (ref "SW2") (pin "1") (pinfunction "O_1") (pintype "passive"))
      (node (ref "TP10") (pin "TP") (pinfunction "TP_TP") (pintype "input"))
      (node (ref "VR4") (pin "E") (pinfunction "E_E") (pintype "passive"))
    )
    (net (code "102") (name "STRIP") (class "Default")
      (node (ref "H1") (pin "B2,8") (pinfunction "MOUNT_B2,8") (pintype "passive"))
      (node (ref "Q27") (pin "B") (pinfunction "B_B") (pintype "passive"))
      (node (ref "R13") (pin "1") (pinfunction "1_1") (pintype "passive"))
      (node (ref "R15") (pin "1") (pinfunction "1_1") (pintype "passive"))
      (node (ref "R5") (pin "1") (pinfunction "1_1") (pintype "passive"))
      (node (ref "R55") (pin "2") (pinfunction "2_2") (pintype "passive"))
      (node (ref "TP3") (pin "TP") (pinfunction "TP_TP") (pintype "input"))
    )
    (net (code "103") (name "TRI") (class "Default")
      (node (ref "C24") (pin "2") (pinfunction "2_2") (pintype "passive"))
      (node (ref "IC5") (pin "7") (pinfunction "OUT_7") (pintype "output"))
      (node (ref "R45") (pin "1") (pinfunction "1_1") (pintype "passive"))
      (node (ref "SW2") (pin "3") (pinfunction "S_3") (pintype "passive"))
      (node (ref "TP12") (pin "TP") (pinfunction "TP_TP") (pintype "input"))
    )
    (net (code "104") (name "V+") (class "Default")
      (node (ref "C26") (pin "+") (pinfunction "+_+") (pintype "passive"))
      (node (ref "C27") (pin "1") (pinfunction "1_1") (pintype "passive"))
      (node (ref "IC4") (pin "6") (pinfunction "VS_6") (pintype "power_in"))
      (node (ref "IC6") (pin "3") (pinfunction "VIN_3") (pintype "input"))
      (node (ref "R60") (pin "2") (pinfunction "2_2") (pintype "passive"))
      (node (ref "SW1") (pin "0") (pinfunction "T3_0") (pintype "passive"))
      (node (ref "SW1") (pin "2") (pinfunction "T2_2") (pintype "passive"))
      (node (ref "TP13") (pin "TP") (pinfunction "TP_TP") (pintype "input"))
    )
    (net (code "105") (name "VCF_OUT") (class "Default")
      (node (ref "C31") (pin "1") (pinfunction "1_1") (pintype "passive"))
      (node (ref "IC1") (pin "7") (pinfunction "OUT_7") (pintype "output"))
      (node (ref "R2") (pin "2") (pinfunction "2_2") (pintype "passive"))
      (node (ref "TP2") (pin "TP") (pinfunction "TP_TP") (pintype "input"))
      (node (ref "VR1") (pin "E") (pinfunction "E_E") (pintype "passive"))
    )
    (net (code "106") (name "VCO") (class "Default")
      (node (ref "C19") (pin "1") (pinfunction "1_1") (pintype "passive"))
      (node (ref "Q19") (pin "E") (pinfunction "E_E") (pintype "passive"))
      (node (ref "R26") (pin "1") (pinfunction "1_1") (pintype "passive"))
      (node (ref "R37") (pin "2") (pinfunction "2_2") (pintype "passive"))
      (node (ref "TP7") (pin "TP") (pinfunction "TP_TP") (pintype "input"))
    )
    (net (code "107") (name "unconnected-(J2-3-Pad2)") (class "Default")
      (node (ref "J2") (pin "2") (pinfunction "3_2") (pintype "passive"))
    )
    (net (code "108") (name "unconnected-(SW1A-T1-Pad7)") (class "Default")
      (node (ref "SW1") (pin "7") (pinfunction "T1_7") (pintype "passive"))
    )
    (net (code "109") (name "unconnected-(SW1B-T1-Pad3)") (class "Default")
      (node (ref "SW1") (pin "3") (pinfunction "T1_3") (pintype "passive"))
    )
  )
)
